# Connectors.net
KiCad netlist of a schematic drawn in Altium Designer
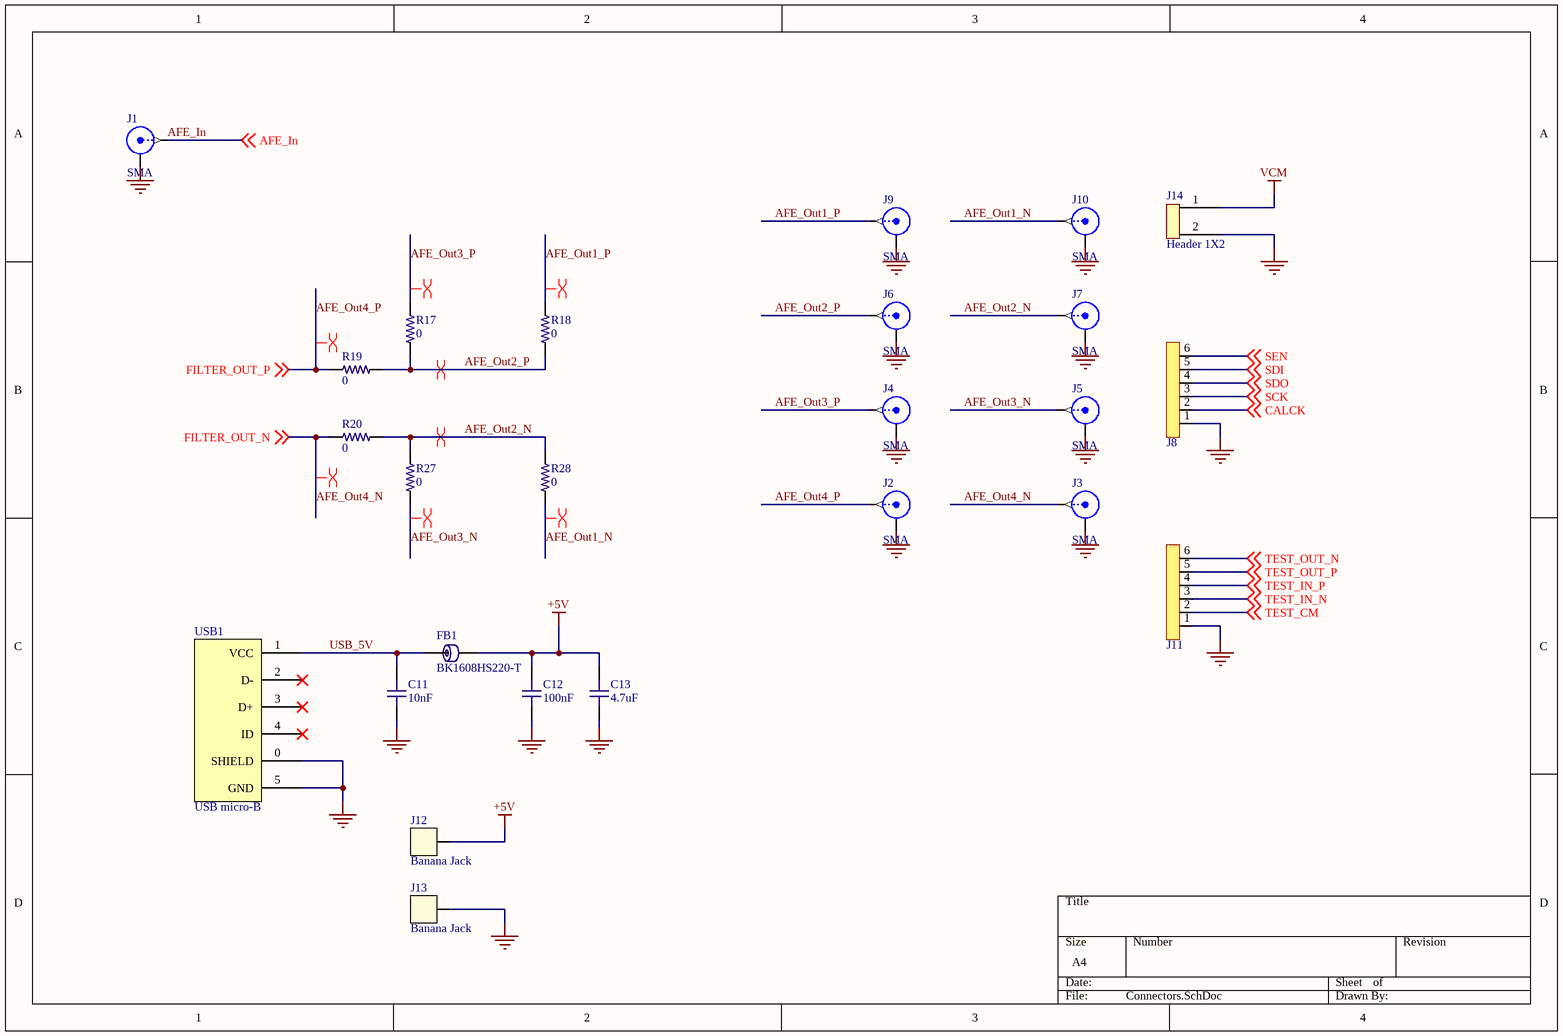
[diagram p0: Connectors.SchDoc]

(export (version "E")
  (design (tool "Eeschema 10.0.6"))
  (components
    (comp (ref "C11")
      (value "10nF")
      (footprint "C0402-IPC")
      (description "Chip Capacitor, 0402, 10nF, 16V, X7R")
      (fields (field (name "Comment") "C0402 10nF 16V X7R"))
      (libsource (lib "Capacitors") (part "C0402 10nF 16V X7R"))
    )
    (comp (ref "C12")
      (value "100nF")
      (footprint "C0402-IPC")
      (description "Chip Capacitor, 0402, 100nF, 16V, X7R")
      (fields (field (name "Comment") "C0402 100nF 16V X7R"))
      (libsource (lib "Capacitors") (part "C0402 100nF 16V X7R"))
    )
    (comp (ref "C13")
      (value "4.7uF")
      (footprint "C0603-HIGH-DENSITY")
      (description "Chip Capacitor, 0603, 4.7uF, 25V, X5R")
      (fields (field (name "Comment") "4.7uF, 25V, X5R, 0603"))
      (libsource (lib "Capacitors") (part "C0603 4.7uF 25V X5R"))
    )
    (comp (ref "FB1")
      (value "BK1608HS220-T")
      (footprint "L0603")
      (description "Ferrite Beads Multi-Layer 22Ohm 25% 100MHz 1.5A 0.05Ohm DCR 0603 T/R")
      (fields (field (name "MANUFACTURER") "Taiyo Yuden") (field (name "TOLERANCE") "25%"))
      (libsource (lib "AFE") (part "BK1608HS220-T"))
    )
    (comp (ref "J1")
      (value "SMA")
      (footprint "SMA Edge Launch (Horizontal)")
      (description "SMA Connector")
      (libsource (lib "Connectors") (part "SMA"))
    )
    (comp (ref "J2")
      (value "SMA")
      (footprint "SMA Edge Launch (Horizontal)")
      (description "SMA Connector")
      (libsource (lib "Connectors") (part "SMA"))
    )
    (comp (ref "J3")
      (value "SMA")
      (footprint "SMA Edge Launch (Horizontal)")
      (description "SMA Connector")
      (libsource (lib "Connectors") (part "SMA"))
    )
    (comp (ref "J4")
      (value "SMA")
      (footprint "SMA Edge Launch (Horizontal)")
      (description "SMA Connector")
      (libsource (lib "Connectors") (part "SMA"))
    )
    (comp (ref "J5")
      (value "SMA")
      (footprint "SMA Edge Launch (Horizontal)")
      (description "SMA Connector")
      (libsource (lib "Connectors") (part "SMA"))
    )
    (comp (ref "J6")
      (value "SMA")
      (footprint "SMA Edge Launch (Horizontal)")
      (description "SMA Connector")
      (libsource (lib "Connectors") (part "SMA"))
    )
    (comp (ref "J7")
      (value "SMA")
      (footprint "SMA Edge Launch (Horizontal)")
      (description "SMA Connector")
      (libsource (lib "Connectors") (part "SMA"))
    )
    (comp (ref "J8")
      (value "100 mil hdr 6 pos")
      (footprint "100MIL HDR 6 POS")
      (description "Header, 100 mil, 6pos, tin")
      (libsource (lib "Connectors") (part "100 mil hdr 6 pos"))
    )
    (comp (ref "J9")
      (value "SMA")
      (footprint "SMA Edge Launch (Horizontal)")
      (description "SMA Connector")
      (libsource (lib "Connectors") (part "SMA"))
    )
    (comp (ref "J10")
      (value "SMA")
      (footprint "SMA Edge Launch (Horizontal)")
      (description "SMA Connector")
      (libsource (lib "Connectors") (part "SMA"))
    )
    (comp (ref "J11")
      (value "100 mil hdr 6 pos")
      (footprint "100MIL HDR 6 POS")
      (description "Header, 100 mil, 6pos, tin")
      (libsource (lib "Connectors") (part "100 mil hdr 6 pos"))
    )
    (comp (ref "J12")
      (value "Banana Jack")
      (footprint "Banana Jack")
      (description "JACK NON-INSULATED .350\"")
      (libsource (lib "Connectors") (part "Banana Jack"))
    )
    (comp (ref "J13")
      (value "Banana Jack")
      (footprint "Banana Jack")
      (description "JACK NON-INSULATED .350\"")
      (libsource (lib "Connectors") (part "Banana Jack"))
    )
    (comp (ref "J14")
      (value "Header 1X2")
      (footprint "Header 1x2 TH Pitch 2.54mm")
      (libsource (lib "Connectors") (part "Header 1X2"))
    )
    (comp (ref "R17")
      (value "0")
      (footprint "R0603-IPC")
      (description "RES SMD 0 OHM JUMPER 1/10W 0603")
      (fields (field (name "Comment") "R0603 0"))
      (libsource (lib "Resistors") (part "R0603 0"))
    )
    (comp (ref "R18")
      (value "0")
      (footprint "R0603-IPC")
      (description "RES SMD 0 OHM JUMPER 1/10W 0603")
      (fields (field (name "Comment") "R0603 0"))
      (libsource (lib "Resistors") (part "R0603 0"))
    )
    (comp (ref "R19")
      (value "0")
      (footprint "R0603-IPC")
      (description "RES SMD 0 OHM JUMPER 1/10W 0603")
      (fields (field (name "Comment") "R0603 0"))
      (libsource (lib "Resistors") (part "R0603 0"))
    )
    (comp (ref "R20")
      (value "0")
      (footprint "R0603-IPC")
      (description "RES SMD 0 OHM JUMPER 1/10W 0603")
      (fields (field (name "Comment") "R0603 0"))
      (libsource (lib "Resistors") (part "R0603 0"))
    )
    (comp (ref "R27")
      (value "0")
      (footprint "R0603-IPC")
      (description "RES SMD 0 OHM JUMPER 1/10W 0603")
      (fields (field (name "Comment") "R0603 0"))
      (libsource (lib "Resistors") (part "R0603 0"))
    )
    (comp (ref "R28")
      (value "0")
      (footprint "R0603-IPC")
      (description "RES SMD 0 OHM JUMPER 1/10W 0603")
      (fields (field (name "Comment") "R0603 0"))
      (libsource (lib "Resistors") (part "R0603 0"))
    )
    (comp (ref "USB1")
      (value "USB micro-B")
      (footprint "USB-MicroB")
      (description "CONN RCPT USB TYPE B 3A")
      (fields
        (field (name "MANUFACTURER PART NUMBER") "629105150521")
        (field (name "MANUFACTURER") "Wurth Electronics Inc.")
      )
      (libsource (lib "Connectors") (part "USB micro-B"))
    )
  )
  (nets
    (net (code "1") (name "+5V") (class "Default")
      (node (ref "C12") (pin "2") (pintype "passive"))
      (node (ref "C13") (pin "2") (pintype "passive"))
      (node (ref "FB1") (pin "2") (pintype "passive"))
      (node (ref "J12") (pin "1") (pinfunction "1_1") (pintype "passive"))
    )
    (net (code "2") (name "/AFE_Out1_N") (class "Default")
      (node (ref "J10") (pin "1") (pinfunction "X_1") (pintype "output"))
      (node (ref "R28") (pin "1") (pintype "passive"))
    )
    (net (code "3") (name "/AFE_Out1_P") (class "Default")
      (node (ref "J9") (pin "1") (pinfunction "X_1") (pintype "output"))
      (node (ref "R18") (pin "2") (pintype "passive"))
    )
    (net (code "4") (name "/AFE_Out2_N") (class "Default")
      (node (ref "J7") (pin "1") (pinfunction "X_1") (pintype "output"))
      (node (ref "R20") (pin "2") (pintype "passive"))
      (node (ref "R27") (pin "2") (pintype "passive"))
      (node (ref "R28") (pin "2") (pintype "passive"))
    )
    (net (code "5") (name "/AFE_Out2_P") (class "Default")
      (node (ref "J6") (pin "1") (pinfunction "X_1") (pintype "output"))
      (node (ref "R17") (pin "1") (pintype "passive"))
      (node (ref "R18") (pin "1") (pintype "passive"))
      (node (ref "R19") (pin "2") (pintype "passive"))
    )
    (net (code "6") (name "/AFE_Out3_N") (class "Default")
      (node (ref "J5") (pin "1") (pinfunction "X_1") (pintype "output"))
      (node (ref "R27") (pin "1") (pintype "passive"))
    )
    (net (code "7") (name "/AFE_Out3_P") (class "Default")
      (node (ref "J4") (pin "1") (pinfunction "X_1") (pintype "output"))
      (node (ref "R17") (pin "2") (pintype "passive"))
    )
    (net (code "8") (name "/USB_5V") (class "Default")
      (node (ref "C11") (pin "2") (pintype "passive"))
      (node (ref "FB1") (pin "1") (pintype "passive"))
      (node (ref "USB1") (pin "1") (pinfunction "VCC_1") (pintype "passive"))
    )
    (net (code "9") (name "AFE_In") (class "Default")
      (node (ref "J1") (pin "1") (pinfunction "X_1") (pintype "output"))
    )
    (net (code "10") (name "CALCK") (class "Default")
      (node (ref "J8") (pin "2") (pinfunction "2_2") (pintype "passive"))
    )
    (net (code "11") (name "FILTER_OUT_N") (class "Default")
      (node (ref "J3") (pin "1") (pinfunction "X_1") (pintype "output"))
      (node (ref "R20") (pin "1") (pintype "passive"))
    )
    (net (code "12") (name "FILTER_OUT_P") (class "Default")
      (node (ref "J2") (pin "1") (pinfunction "X_1") (pintype "output"))
      (node (ref "R19") (pin "1") (pintype "passive"))
    )
    (net (code "13") (name "GND") (class "Default")
      (node (ref "C11") (pin "1") (pintype "passive"))
      (node (ref "C12") (pin "1") (pintype "passive"))
      (node (ref "C13") (pin "1") (pintype "passive"))
      (node (ref "J1") (pin "2") (pinfunction "Y_2") (pintype "power_in"))
      (node (ref "J10") (pin "2") (pinfunction "Y_2") (pintype "power_in"))
      (node (ref "J11") (pin "1") (pinfunction "1_1") (pintype "passive"))
      (node (ref "J13") (pin "1") (pinfunction "1_1") (pintype "passive"))
      (node (ref "J14") (pin "2") (pintype "passive"))
      (node (ref "J2") (pin "2") (pinfunction "Y_2") (pintype "power_in"))
      (node (ref "J3") (pin "2") (pinfunction "Y_2") (pintype "power_in"))
      (node (ref "J4") (pin "2") (pinfunction "Y_2") (pintype "power_in"))
      (node (ref "J5") (pin "2") (pinfunction "Y_2") (pintype "power_in"))
      (node (ref "J6") (pin "2") (pinfunction "Y_2") (pintype "power_in"))
      (node (ref "J7") (pin "2") (pinfunction "Y_2") (pintype "power_in"))
      (node (ref "J8") (pin "1") (pinfunction "1_1") (pintype "passive"))
      (node (ref "J9") (pin "2") (pinfunction "Y_2") (pintype "power_in"))
      (node (ref "USB1") (pin "0") (pinfunction "SHIELD_0") (pintype "passive"))
      (node (ref "USB1") (pin "5") (pinfunction "GND_5") (pintype "passive"))
    )
    (net (code "14") (name "SCK") (class "Default")
      (node (ref "J8") (pin "3") (pinfunction "3_3") (pintype "passive"))
    )
    (net (code "15") (name "SDI") (class "Default")
      (node (ref "J8") (pin "5") (pinfunction "5_5") (pintype "passive"))
    )
    (net (code "16") (name "SDO") (class "Default")
      (node (ref "J8") (pin "4") (pinfunction "4_4") (pintype "passive"))
    )
    (net (code "17") (name "SEN") (class "Default")
      (node (ref "J8") (pin "6") (pinfunction "6_6") (pintype "passive"))
    )
    (net (code "18") (name "TEST_CM") (class "Default")
      (node (ref "J11") (pin "2") (pinfunction "2_2") (pintype "passive"))
    )
    (net (code "19") (name "TEST_IN_N") (class "Default")
      (node (ref "J11") (pin "3") (pinfunction "3_3") (pintype "passive"))
    )
    (net (code "20") (name "TEST_IN_P") (class "Default")
      (node (ref "J11") (pin "4") (pinfunction "4_4") (pintype "passive"))
    )
    (net (code "21") (name "TEST_OUT_N") (class "Default")
      (node (ref "J11") (pin "6") (pinfunction "6_6") (pintype "passive"))
    )
    (net (code "22") (name "TEST_OUT_P") (class "Default")
      (node (ref "J11") (pin "5") (pinfunction "5_5") (pintype "passive"))
    )
    (net (code "23") (name "VCM") (class "Default") (node (ref "J14") (pin "1") (pintype "passive")))
    (net (code "24") (name "unconnected-(USB1-D+-Pad3)") (class "Default")
      (node (ref "USB1") (pin "3") (pinfunction "D+_3") (pintype "passive+no_connect"))
    )
    (net (code "25") (name "unconnected-(USB1-D--Pad2)") (class "Default")
      (node (ref "USB1") (pin "2") (pinfunction "D-_2") (pintype "passive+no_connect"))
    )
    (net (code "26") (name "unconnected-(USB1-ID-Pad4)") (class "Default")
      (node (ref "USB1") (pin "4") (pinfunction "ID_4") (pintype "passive+no_connect"))
    )
  )
)
